# Encoder_RJ45.net
KiCad netlist of a schematic drawn in Altium Designer
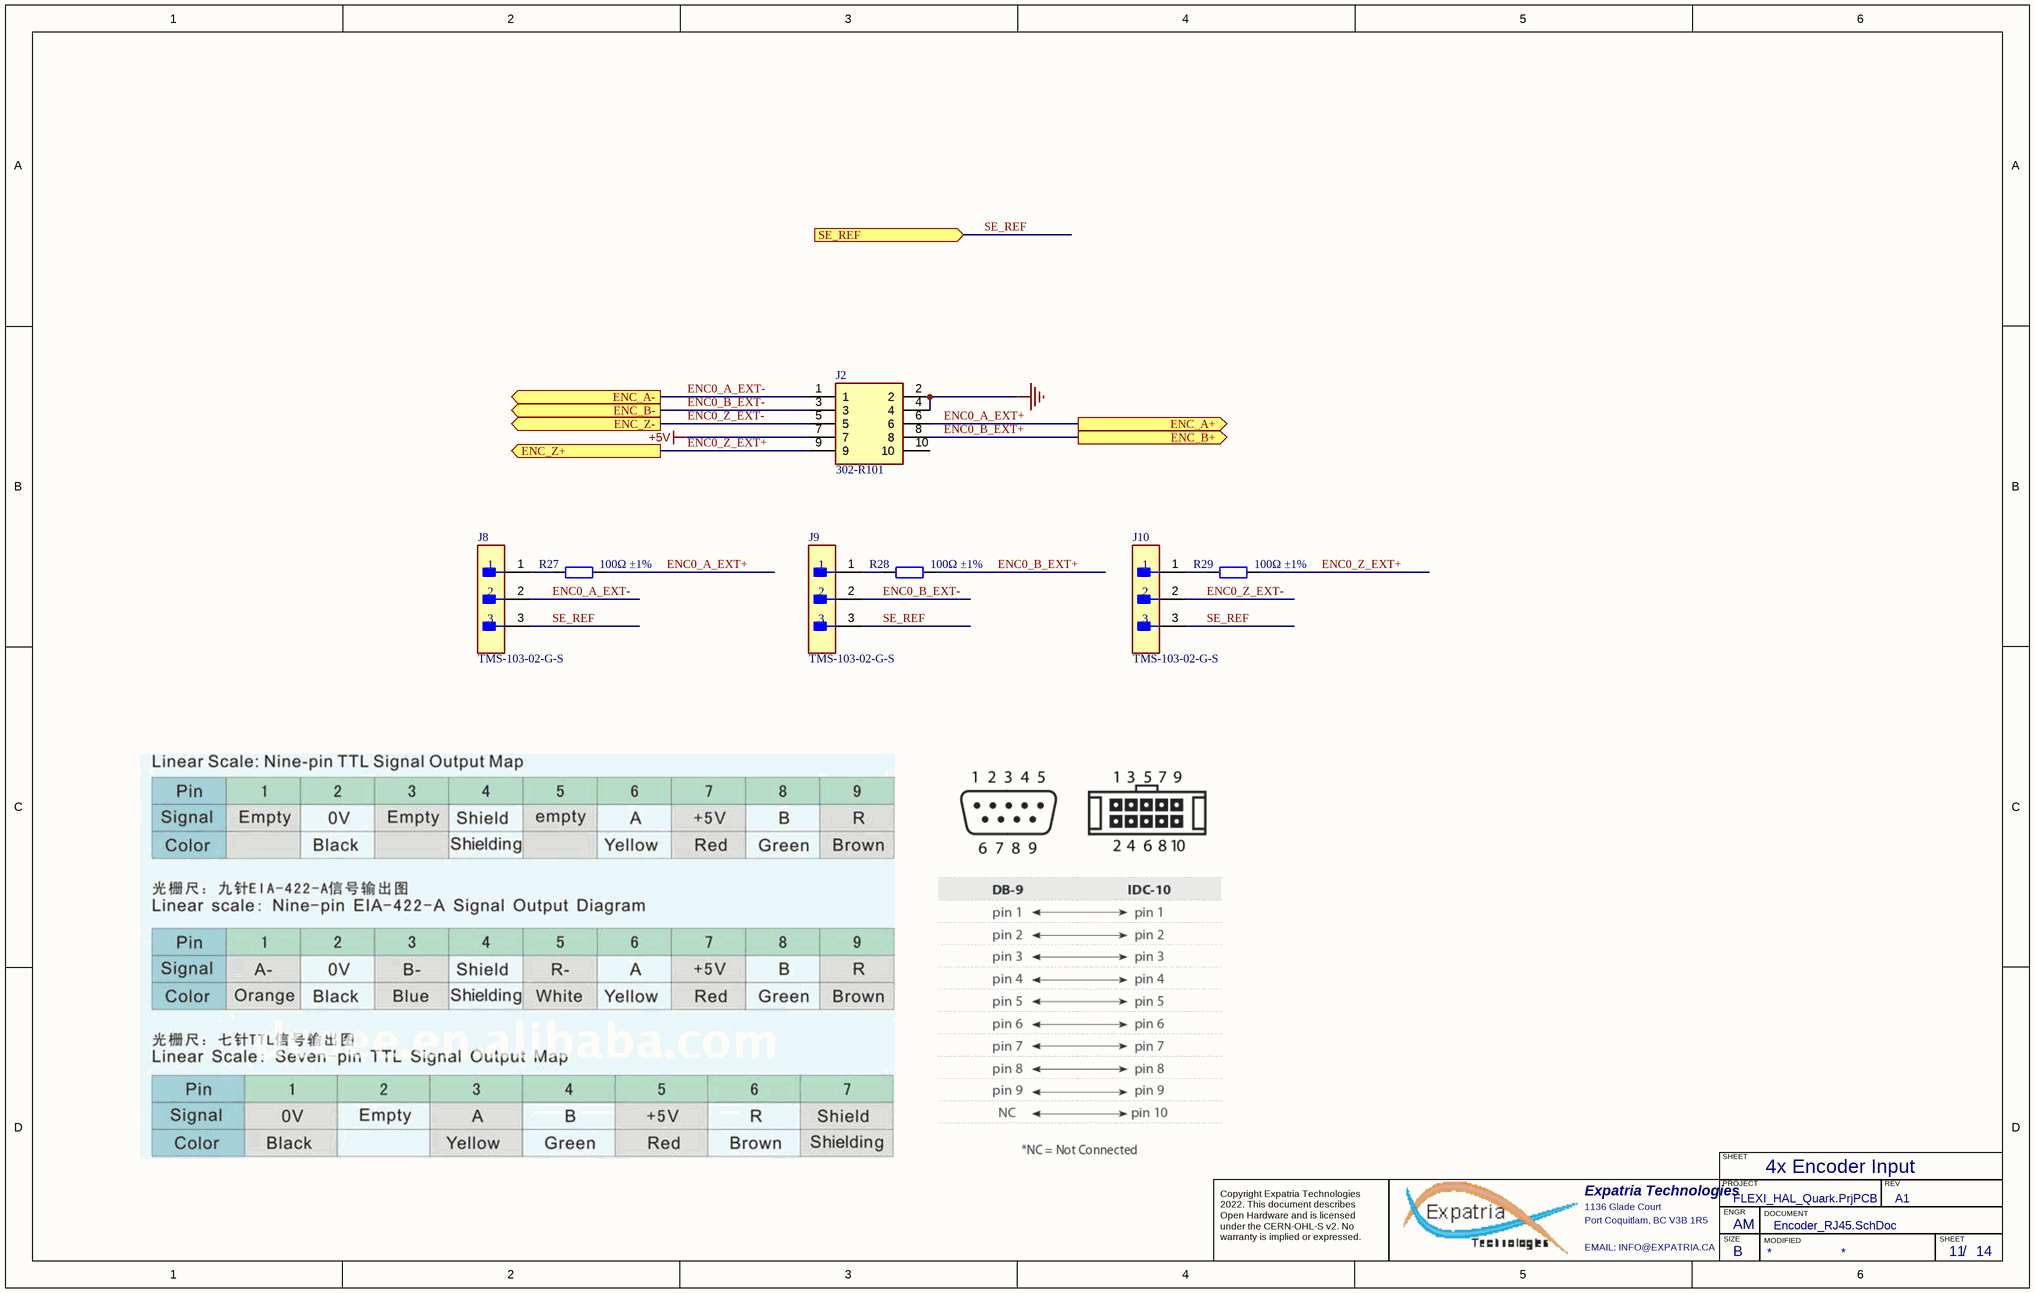
[diagram p0: Encoder_RJ45.SchDoc]

(export (version "E")
  (design (tool "Eeschema 10.0.6"))
  (components
    (comp (ref "J2")
      (value "302-R101")
      (footprint "SamacSys:SHDRRA10W66P254_2X5_2032X910X910P")
      (description "Connector")
      (libsource (lib "*") (part "302-R101"))
    )
    (comp (ref "J8")
      (value "TMS-103-02-G-S")
      (footprint "FP-TMS-103-02-G-S-MFG")
      (description "CONN HEADER VERT 3POS 1.27MM")
      (libsource (lib "Altium Content Vault") (part "0d3f023dd272f625e17a2be33dea85f"))
    )
    (comp (ref "J9")
      (value "TMS-103-02-G-S")
      (footprint "FP-TMS-103-02-G-S-MFG")
      (description "CONN HEADER VERT 3POS 1.27MM")
      (libsource (lib "Altium Content Vault") (part "0d3f023dd272f625e17a2be33dea85f"))
    )
    (comp (ref "J10")
      (value "TMS-103-02-G-S")
      (footprint "FP-TMS-103-02-G-S-MFG")
      (description "CONN HEADER VERT 3POS 1.27MM")
      (libsource (lib "Altium Content Vault") (part "0d3f023dd272f625e17a2be33dea85f"))
    )
    (comp (ref "R27")
      (value "100Ω ±1%")
      (footprint "0402_R")
      (description "Chip resistor")
      (fields (field (name "MANUFACTURER") "Uniroyal Elec") (field (name "PARTNUMBER") "0402WGF1000TCE"))
      (libsource (lib "RES") (part "0402 100R (1000) 1%"))
    )
    (comp (ref "R28")
      (value "100Ω ±1%")
      (footprint "0402_R")
      (description "Chip resistor")
      (fields (field (name "MANUFACTURER") "Uniroyal Elec") (field (name "PARTNUMBER") "0402WGF1000TCE"))
      (libsource (lib "RES") (part "0402 100R (1000) 1%"))
    )
    (comp (ref "R29")
      (value "100Ω ±1%")
      (footprint "0402_R")
      (description "Chip resistor")
      (fields (field (name "MANUFACTURER") "Uniroyal Elec") (field (name "PARTNUMBER") "0402WGF1000TCE"))
      (libsource (lib "RES") (part "0402 100R (1000) 1%"))
    )
  )
  (nets
    (net (code "1") (name "+5V") (class "Default")
      (node (ref "J2") (pin "7") (pinfunction "7_7") (pintype "passive"))
    )
    (net (code "2") (name "/ENC0_A_EXT+") (class "Default")
      (node (ref "J2") (pin "6") (pinfunction "6_6") (pintype "passive"))
      (node (ref "R27") (pin "2") (pinfunction "2_2") (pintype "passive"))
    )
    (net (code "3") (name "/ENC0_A_EXT-") (class "Default")
      (node (ref "J2") (pin "1") (pinfunction "1_1") (pintype "passive"))
      (node (ref "J8") (pin "2") (pinfunction "2_2") (pintype "passive"))
    )
    (net (code "4") (name "/ENC0_B_EXT+") (class "Default")
      (node (ref "J2") (pin "8") (pinfunction "8_8") (pintype "passive"))
      (node (ref "R28") (pin "2") (pinfunction "2_2") (pintype "passive"))
    )
    (net (code "5") (name "/ENC0_B_EXT-") (class "Default")
      (node (ref "J2") (pin "3") (pinfunction "3_3") (pintype "passive"))
      (node (ref "J9") (pin "2") (pinfunction "2_2") (pintype "passive"))
    )
    (net (code "6") (name "/ENC0_Z_EXT+") (class "Default")
      (node (ref "J2") (pin "9") (pinfunction "9_9") (pintype "passive"))
      (node (ref "R29") (pin "2") (pinfunction "2_2") (pintype "passive"))
    )
    (net (code "7") (name "/ENC0_Z_EXT-") (class "Default")
      (node (ref "J10") (pin "2") (pinfunction "2_2") (pintype "passive"))
      (node (ref "J2") (pin "5") (pinfunction "5_5") (pintype "passive"))
    )
    (net (code "8") (name "/SE_REF") (class "Default")
      (node (ref "J10") (pin "3") (pinfunction "3_3") (pintype "passive"))
      (node (ref "J8") (pin "3") (pinfunction "3_3") (pintype "passive"))
      (node (ref "J9") (pin "3") (pinfunction "3_3") (pintype "passive"))
    )
    (net (code "9") (name "GND") (class "Default")
      (node (ref "J2") (pin "2") (pinfunction "2_2") (pintype "passive"))
      (node (ref "J2") (pin "4") (pinfunction "4_4") (pintype "passive"))
    )
    (net (code "10") (name "Net-(J8-Pad1)") (class "Default")
      (node (ref "J8") (pin "1") (pinfunction "1_1") (pintype "passive"))
      (node (ref "R27") (pin "1") (pinfunction "1_1") (pintype "passive"))
    )
    (net (code "11") (name "Net-(J9-Pad1)") (class "Default")
      (node (ref "J9") (pin "1") (pinfunction "1_1") (pintype "passive"))
      (node (ref "R28") (pin "1") (pinfunction "1_1") (pintype "passive"))
    )
    (net (code "12") (name "Net-(J10-Pad1)") (class "Default")
      (node (ref "J10") (pin "1") (pinfunction "1_1") (pintype "passive"))
      (node (ref "R29") (pin "1") (pinfunction "1_1") (pintype "passive"))
    )
    (net (code "13") (name "unconnected-(J2-Pad10)") (class "Default")
      (node (ref "J2") (pin "10") (pinfunction "10_10") (pintype "passive"))
    )
  )
)
